# water_sensor_schematic.net
KiCad netlist of a schematic drawn in Altium Designer
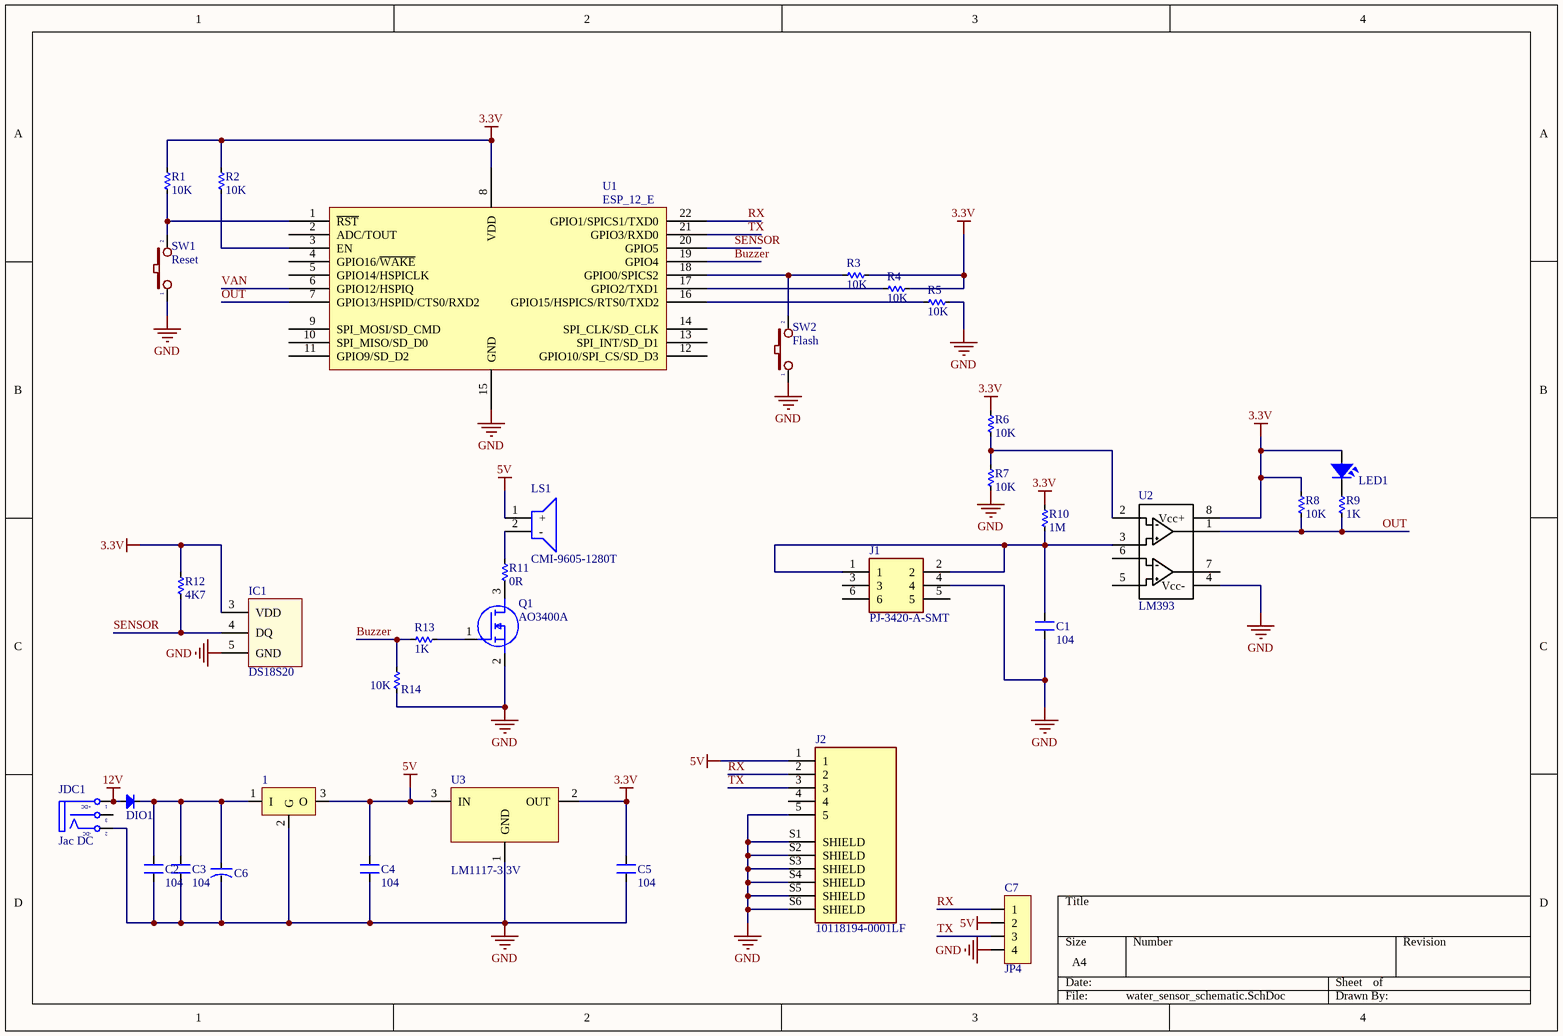
[diagram p0: water_sensor_schematic.SchDoc]

(export (version "E")
  (design (tool "Eeschema 10.0.6"))
  (components
    (comp (ref "1")
      (value "LM78xx")
      (footprint "TO252-123")
      (description "Positive Voltage Regulator")
      (fields (field (name "PUBLISHER") "Altium Limited"))
      (libsource (lib "LIBRARY") (part "LM78xx"))
    )
    (comp (ref "C1")
      (value "104")
      (footprint "SM-CAP-0805")
      (fields (field (name "DESIGNED BY") "VanDungEvn"))
      (libsource (lib "electronicvn-library1") (part "CN"))
    )
    (comp (ref "C2")
      (value "104")
      (footprint "SM-CAP-0805")
      (fields (field (name "DESIGNED BY") "VanDungEvn"))
      (libsource (lib "electronicvn-library1") (part "CN"))
    )
    (comp (ref "C3")
      (value "104")
      (footprint "SM-CAP-0805")
      (fields (field (name "DESIGNED BY") "VanDungEvn"))
      (libsource (lib "electronicvn-library1") (part "CN"))
    )
    (comp (ref "C4")
      (value "104")
      (footprint "SM-CAP-0805")
      (fields (field (name "DESIGNED BY") "VanDungEvn"))
      (libsource (lib "electronicvn-library1") (part "CN"))
    )
    (comp (ref "C5")
      (value "104")
      (footprint "SM-CAP-0805")
      (fields (field (name "DESIGNED BY") "VanDungEvn"))
      (libsource (lib "electronicvn-library1") (part "CN"))
    )
    (comp (ref "C6")
      (value "CN-ALU-SMD")
      (footprint "CAP-ALU-SMD-4.5x5x1.4")
      (description "Polarized Capacitor (Axial)")
      (fields (field (name "PUBLISHER") "Altium Limited"))
      (libsource (lib "LIBTanCN") (part "CN-ALU-SMD"))
    )
    (comp (ref "C7")
      (value "JP4")
      (footprint "JP4-C1T")
      (description "WR-PHD 2.54 mm Angled Socket Header")
      (fields
        (field (name "MANUFACTURER") "Würth Elektronik eiSos GmbH")
        (field (name "PARTNO") "613004143121")
        (field (name "CREATED BY") "Karrer Zheng")
      )
      (libsource (lib "LIBRARY") (part "JP4"))
    )
    (comp (ref "DIO1")
      (value "Diode SMD")
      (footprint "DIO-SMD-106")
      (description "Default Diode")
      (fields (field (name "PUBLISHER") "Altium Limited"))
      (libsource (lib "LIBRARY") (part "Diode SMD"))
    )
    (comp (ref "IC1")
      (value "DS18S20")
      (footprint "DS18S20")
      (description "High Precision  1-Wire® Digital Thermometer")
      (libsource (lib "LIBTanCN") (part "DS18S20"))
    )
    (comp (ref "J1")
      (value "PJ-3420-A-SMT")
      (footprint "SamacSys:PJ3420ASMT")
      (description "Connector")
      (libsource (lib "*") (part "PJ-3420-A-SMT"))
    )
    (comp (ref "J2")
      (value "10118194-0001LF")
      (footprint "AMPHENOL_10118194-0001LF")
      (description "USB - micro B USB 2.0 Receptacle Connector 5 Position Surface Mount, Right Angle; Through Hole")
      (fields (field (name "MF") "Amphenol ICC"))
      (libsource (lib "10118194-0001LF") (part "10118194-0001LF"))
    )
    (comp (ref "JDC1")
      (value "Jac DC")
      (footprint "DC3")
      (description "Jac DC input")
      (libsource (lib "LIBRARY") (part "DCIN"))
    )
    (comp (ref "LED1") (value "LED") (footprint "LED-0805-Blue") (libsource (lib "LIBRARY") (part "LED SMD")))
    (comp (ref "LS1")
      (value "CMI-9605-1280T")
      (footprint "SamacSys:CMI96051280T")
      (description "Loudspeaker or Buzzer")
      (fields (field (name "MOUSER PART NUMBER") "490-CMI-9605-1280T"))
      (libsource (lib "*") (part "CMI-9605-1280T"))
    )
    (comp (ref "Q1")
      (value "AO3400A")
      (footprint "SamacSys:SOT95P280X125-3N")
      (description "MOSFET (N-Channel)")
      (libsource (lib "SamacSys") (part "AO3400A"))
    )
    (comp (ref "R1")
      (value "10K")
      (footprint "RES-SMD-0805")
      (description "Resistor")
      (fields
        (field (name "MANUFACTURER") "Generic Components")
        (field (name "PUBLISHER") "Altium Hobart Technology Centre")
      )
      (libsource (lib "LIBRARY") (part "Res-SMD"))
    )
    (comp (ref "R2")
      (value "10K")
      (footprint "RES-SMD-0805")
      (description "Resistor")
      (fields
        (field (name "MANUFACTURER") "Generic Components")
        (field (name "PUBLISHER") "Altium Hobart Technology Centre")
      )
      (libsource (lib "LIBRARY") (part "Res-SMD"))
    )
    (comp (ref "R3")
      (value "10K")
      (footprint "RES-SMD-0805")
      (description "Resistor")
      (fields
        (field (name "MANUFACTURER") "Generic Components")
        (field (name "PUBLISHER") "Altium Hobart Technology Centre")
      )
      (libsource (lib "LIBRARY") (part "Res-SMD"))
    )
    (comp (ref "R4")
      (value "10K")
      (footprint "RES-SMD-0805")
      (description "Resistor")
      (fields
        (field (name "MANUFACTURER") "Generic Components")
        (field (name "PUBLISHER") "Altium Hobart Technology Centre")
      )
      (libsource (lib "LIBRARY") (part "Res-SMD"))
    )
    (comp (ref "R5")
      (value "10K")
      (footprint "RES-SMD-0805")
      (description "Resistor")
      (fields
        (field (name "MANUFACTURER") "Generic Components")
        (field (name "PUBLISHER") "Altium Hobart Technology Centre")
      )
      (libsource (lib "LIBRARY") (part "Res-SMD"))
    )
    (comp (ref "R6")
      (value "10K")
      (footprint "RES-SMD-0805")
      (description "Resistor")
      (fields
        (field (name "MANUFACTURER") "Generic Components")
        (field (name "PUBLISHER") "Altium Hobart Technology Centre")
      )
      (libsource (lib "LIBRARY") (part "Res-SMD"))
    )
    (comp (ref "R7")
      (value "10K")
      (footprint "RES-SMD-0805")
      (description "Resistor")
      (fields
        (field (name "MANUFACTURER") "Generic Components")
        (field (name "PUBLISHER") "Altium Hobart Technology Centre")
      )
      (libsource (lib "LIBRARY") (part "Res-SMD"))
    )
    (comp (ref "R8")
      (value "10K")
      (footprint "RES-SMD-0805")
      (description "Resistor")
      (fields
        (field (name "MANUFACTURER") "Generic Components")
        (field (name "PUBLISHER") "Altium Hobart Technology Centre")
      )
      (libsource (lib "LIBRARY") (part "Res-SMD"))
    )
    (comp (ref "R9")
      (value "1K")
      (footprint "RES-SMD-0805")
      (description "Resistor")
      (fields
        (field (name "MANUFACTURER") "Generic Components")
        (field (name "PUBLISHER") "Altium Hobart Technology Centre")
      )
      (libsource (lib "LIBRARY") (part "Res-SMD"))
    )
    (comp (ref "R10")
      (value "1M")
      (footprint "RES-SMD-0805")
      (description "Resistor")
      (fields
        (field (name "MANUFACTURER") "Generic Components")
        (field (name "PUBLISHER") "Altium Hobart Technology Centre")
      )
      (libsource (lib "LIBRARY") (part "Res-SMD"))
    )
    (comp (ref "R11")
      (value "0R")
      (footprint "RES-SMD-0805")
      (description "Resistor")
      (fields
        (field (name "MANUFACTURER") "Generic Components")
        (field (name "PUBLISHER") "Altium Hobart Technology Centre")
      )
      (libsource (lib "LIBRARY") (part "Res-SMD"))
    )
    (comp (ref "R12")
      (value "4K7")
      (footprint "RES-SMD-0805")
      (description "Resistor")
      (fields
        (field (name "MANUFACTURER") "Generic Components")
        (field (name "PUBLISHER") "Altium Hobart Technology Centre")
      )
      (libsource (lib "LIBRARY") (part "Res-SMD"))
    )
    (comp (ref "R13")
      (value "1K")
      (footprint "RES-SMD-0805")
      (description "Resistor")
      (fields
        (field (name "MANUFACTURER") "Generic Components")
        (field (name "PUBLISHER") "Altium Hobart Technology Centre")
      )
      (libsource (lib "LIBRARY") (part "Res-SMD"))
    )
    (comp (ref "R14")
      (value "10K")
      (footprint "RES-SMD-0805")
      (description "Resistor")
      (fields
        (field (name "MANUFACTURER") "Generic Components")
        (field (name "PUBLISHER") "Altium Hobart Technology Centre")
      )
      (libsource (lib "LIBRARY") (part "Res-SMD"))
    )
    (comp (ref "SW1")
      (value "Reset")
      (footprint "SW1-SMD")
      (description "Switch button 2 pin")
      (libsource (lib "LIBRARY") (part "SW2"))
    )
    (comp (ref "SW2")
      (value "Flash")
      (footprint "SW-DIP1-1")
      (description "Switch button 2 pin")
      (libsource (lib "LIBRARY") (part "SW2"))
    )
    (comp (ref "U1")
      (value "ESP_12_E")
      (footprint "ESP_12_E")
      (description "ESP-12 Wi-Fi Module by AI-Thinker")
      (libsource (lib "ESP8266") (part "ESP_12_E"))
    )
    (comp (ref "U2")
      (value "LM393")
      (footprint "SO8")
      (description "IC DUAL COMPARATOR")
      (libsource (lib "LIBRARY") (part "LM393"))
    )
    (comp (ref "U3")
      (value "LM1117-3.3V")
      (footprint "SOT223")
      (description "800mA Low-Dropout Linear Regulator")
      (fields (field (name "CREATOR") "Nguyen Ba Bien"))
      (libsource (lib "LIBRARY") (part "LM1117"))
    )
  )
  (nets
    (net (code "1") (name "/Buzzer") (class "Default")
      (node (ref "R13") (pin "2") (pinfunction "2_2") (pintype "passive"))
      (node (ref "R14") (pin "2") (pinfunction "2_2") (pintype "passive"))
      (node (ref "U1") (pin "19") (pinfunction "GPIO4_19") (pintype "passive"))
    )
    (net (code "2") (name "/OUT") (class "Default")
      (node (ref "R8") (pin "2") (pinfunction "2_2") (pintype "passive"))
      (node (ref "R9") (pin "2") (pinfunction "2_2") (pintype "passive"))
      (node (ref "U1") (pin "7") (pinfunction "GPIO13/HSPID/CTS0/RXD2_7") (pintype "passive"))
      (node (ref "U2") (pin "1") (pintype "passive"))
    )
    (net (code "3") (name "/RX") (class "Default")
      (node (ref "C7") (pin "1") (pinfunction "1_1") (pintype "passive"))
      (node (ref "J2") (pin "2") (pinfunction "2_2") (pintype "passive"))
      (node (ref "U1") (pin "22") (pinfunction "GPIO1/SPICS1/TXD0_22") (pintype "passive"))
    )
    (net (code "4") (name "/SENSOR") (class "Default")
      (node (ref "IC1") (pin "4") (pinfunction "DQ_4") (pintype "passive"))
      (node (ref "R12") (pin "2") (pinfunction "2_2") (pintype "passive"))
      (node (ref "U1") (pin "20") (pinfunction "GPIO5_20") (pintype "passive"))
    )
    (net (code "5") (name "/TX") (class "Default")
      (node (ref "C7") (pin "3") (pinfunction "3_3") (pintype "passive"))
      (node (ref "J2") (pin "3") (pinfunction "3_3") (pintype "passive"))
      (node (ref "U1") (pin "21") (pinfunction "GPIO3/RXD0_21") (pintype "passive"))
    )
    (net (code "6") (name "/VAN") (class "Default")
      (node (ref "U1") (pin "6") (pinfunction "GPIO12/HSPIQ_6") (pintype "passive"))
    )
    (net (code "7") (name "3.3V") (class "Default")
      (node (ref "C5") (pin "2") (pinfunction "2_2") (pintype "passive"))
      (node (ref "IC1") (pin "3") (pinfunction "VDD_3") (pintype "passive"))
      (node (ref "LED1") (pin "1") (pinfunction "1_1") (pintype "passive"))
      (node (ref "R1") (pin "1") (pinfunction "1_1") (pintype "passive"))
      (node (ref "R10") (pin "1") (pinfunction "1_1") (pintype "passive"))
      (node (ref "R12") (pin "1") (pinfunction "1_1") (pintype "passive"))
      (node (ref "R2") (pin "1") (pinfunction "1_1") (pintype "passive"))
      (node (ref "R3") (pin "1") (pinfunction "1_1") (pintype "passive"))
      (node (ref "R4") (pin "1") (pinfunction "1_1") (pintype "passive"))
      (node (ref "R6") (pin "1") (pinfunction "1_1") (pintype "passive"))
      (node (ref "R8") (pin "1") (pinfunction "1_1") (pintype "passive"))
      (node (ref "U1") (pin "8") (pinfunction "VDD_8") (pintype "passive"))
      (node (ref "U2") (pin "8") (pinfunction "Vcc+_8") (pintype "passive"))
      (node (ref "U3") (pin "2") (pinfunction "OUT_2") (pintype "passive"))
    )
    (net (code "8") (name "5V") (class "Default")
      (node (ref "1") (pin "3") (pinfunction "O_3") (pintype "power_in"))
      (node (ref "C4") (pin "2") (pinfunction "2_2") (pintype "passive"))
      (node (ref "C7") (pin "2") (pinfunction "2_2") (pintype "passive"))
      (node (ref "J2") (pin "1") (pinfunction "1_1") (pintype "passive"))
      (node (ref "LS1") (pin "1") (pinfunction "+_1") (pintype "passive"))
      (node (ref "U3") (pin "3") (pinfunction "IN_3") (pintype "passive"))
    )
    (net (code "9") (name "12V") (class "Default")
      (node (ref "DIO1") (pin "1") (pinfunction "A_1") (pintype "passive"))
      (node (ref "JDC1") (pin "1") (pinfunction "T_1") (pintype "passive"))
    )
    (net (code "10") (name "GND") (class "Default")
      (node (ref "1") (pin "2") (pinfunction "G_2") (pintype "power_in"))
      (node (ref "C1") (pin "1") (pinfunction "1_1") (pintype "passive"))
      (node (ref "C2") (pin "1") (pinfunction "1_1") (pintype "passive"))
      (node (ref "C3") (pin "1") (pinfunction "1_1") (pintype "passive"))
      (node (ref "C4") (pin "1") (pinfunction "1_1") (pintype "passive"))
      (node (ref "C5") (pin "1") (pinfunction "1_1") (pintype "passive"))
      (node (ref "C6") (pin "2") (pinfunction "2_2") (pintype "passive"))
      (node (ref "C7") (pin "4") (pinfunction "4_4") (pintype "passive"))
      (node (ref "IC1") (pin "5") (pinfunction "GND_5") (pintype "passive"))
      (node (ref "J1") (pin "4") (pinfunction "4_4") (pintype "passive"))
      (node (ref "J2") (pin "5") (pinfunction "5_5") (pintype "passive"))
      (node (ref "J2") (pin "S1") (pinfunction "SHIELD_S1") (pintype "passive"))
      (node (ref "J2") (pin "S2") (pinfunction "SHIELD_S2") (pintype "passive"))
      (node (ref "J2") (pin "S3") (pinfunction "SHIELD_S3") (pintype "passive"))
      (node (ref "J2") (pin "S4") (pinfunction "SHIELD_S4") (pintype "passive"))
      (node (ref "J2") (pin "S5") (pinfunction "SHIELD_S5") (pintype "passive"))
      (node (ref "J2") (pin "S6") (pinfunction "SHIELD_S6") (pintype "passive"))
      (node (ref "JDC1") (pin "2") (pinfunction "TN_2") (pintype "passive"))
      (node (ref "Q1") (pin "2") (pinfunction "S_2") (pintype "passive"))
      (node (ref "R14") (pin "1") (pinfunction "1_1") (pintype "passive"))
      (node (ref "R5") (pin "1") (pinfunction "1_1") (pintype "passive"))
      (node (ref "R7") (pin "2") (pinfunction "2_2") (pintype "passive"))
      (node (ref "SW1") (pin "1") (pinfunction "1_1") (pintype "passive"))
      (node (ref "SW2") (pin "1") (pinfunction "1_1") (pintype "passive"))
      (node (ref "U1") (pin "15") (pinfunction "GND_15") (pintype "passive"))
      (node (ref "U2") (pin "4") (pinfunction "Vcc-_4") (pintype "passive"))
      (node (ref "U3") (pin "1") (pinfunction "GND_1") (pintype "passive"))
    )
    (net (code "11") (name "Net-(1-I)") (class "Default")
      (node (ref "1") (pin "1") (pinfunction "I_1") (pintype "power_in"))
      (node (ref "C2") (pin "2") (pinfunction "2_2") (pintype "passive"))
      (node (ref "C3") (pin "2") (pinfunction "2_2") (pintype "passive"))
      (node (ref "C6") (pin "1") (pinfunction "1_1") (pintype "passive"))
      (node (ref "DIO1") (pin "2") (pinfunction "K_2") (pintype "passive"))
    )
    (net (code "12") (name "Net-(C1-Pad2)") (class "Default")
      (node (ref "C1") (pin "2") (pinfunction "2_2") (pintype "passive"))
      (node (ref "J1") (pin "1") (pinfunction "1_1") (pintype "passive"))
      (node (ref "J1") (pin "2") (pinfunction "2_2") (pintype "passive"))
      (node (ref "R10") (pin "2") (pinfunction "2_2") (pintype "passive"))
      (node (ref "U2") (pin "3") (pintype "passive"))
    )
    (net (code "13") (name "Net-(LED1-Pad2)") (class "Default")
      (node (ref "LED1") (pin "2") (pinfunction "2_2") (pintype "passive"))
      (node (ref "R9") (pin "1") (pinfunction "1_1") (pintype "passive"))
    )
    (net (code "14") (name "Net-(LS1--)") (class "Default")
      (node (ref "LS1") (pin "2") (pinfunction "-_2") (pintype "passive"))
      (node (ref "R11") (pin "1") (pinfunction "1_1") (pintype "passive"))
    )
    (net (code "15") (name "Net-(Q1-D)") (class "Default")
      (node (ref "Q1") (pin "3") (pinfunction "D_3") (pintype "passive"))
      (node (ref "R11") (pin "2") (pinfunction "2_2") (pintype "passive"))
    )
    (net (code "16") (name "Net-(Q1-G)") (class "Default")
      (node (ref "Q1") (pin "1") (pinfunction "G_1") (pintype "passive"))
      (node (ref "R13") (pin "1") (pinfunction "1_1") (pintype "passive"))
    )
    (net (code "17") (name "Net-(R6-Pad2)") (class "Default")
      (node (ref "R6") (pin "2") (pinfunction "2_2") (pintype "passive"))
      (node (ref "R7") (pin "1") (pinfunction "1_1") (pintype "passive"))
      (node (ref "U2") (pin "2") (pintype "passive"))
    )
    (net (code "18") (name "Net-(U1-EN)") (class "Default")
      (node (ref "R2") (pin "2") (pinfunction "2_2") (pintype "passive"))
      (node (ref "U1") (pin "3") (pinfunction "EN_3") (pintype "passive"))
    )
    (net (code "19") (name "Net-(U1-GPIO0{slash}SPICS2)") (class "Default")
      (node (ref "R3") (pin "2") (pinfunction "2_2") (pintype "passive"))
      (node (ref "SW2") (pin "2") (pinfunction "2_2") (pintype "passive"))
      (node (ref "U1") (pin "18") (pinfunction "GPIO0/SPICS2_18") (pintype "passive"))
    )
    (net (code "20") (name "Net-(U1-GPIO2{slash}TXD1)") (class "Default")
      (node (ref "R4") (pin "2") (pinfunction "2_2") (pintype "passive"))
      (node (ref "U1") (pin "17") (pinfunction "GPIO2/TXD1_17") (pintype "passive"))
    )
    (net (code "21") (name "Net-(U1-GPIO15{slash}HSPICS{slash}RTS0{slash}TXD2)") (class "Default")
      (node (ref "R5") (pin "2") (pinfunction "2_2") (pintype "passive"))
      (node (ref "U1") (pin "16") (pinfunction "GPIO15/HSPICS/RTS0/TXD2_16") (pintype "passive"))
    )
    (net (code "22") (name "Net-(U1-~{RST})") (class "Default")
      (node (ref "R1") (pin "2") (pinfunction "2_2") (pintype "passive"))
      (node (ref "SW1") (pin "2") (pinfunction "2_2") (pintype "passive"))
      (node (ref "U1") (pin "1") (pinfunction "~{RST}_1") (pintype "passive"))
    )
    (net (code "23") (name "unconnected-(J1-Pad3)") (class "Default")
      (node (ref "J1") (pin "3") (pinfunction "3_3") (pintype "passive"))
    )
    (net (code "24") (name "unconnected-(J1-Pad5)") (class "Default")
      (node (ref "J1") (pin "5") (pinfunction "5_5") (pintype "passive"))
    )
    (net (code "25") (name "unconnected-(J1-Pad6)") (class "Default")
      (node (ref "J1") (pin "6") (pinfunction "6_6") (pintype "passive"))
    )
    (net (code "26") (name "unconnected-(J2-Pad4)") (class "Default")
      (node (ref "J2") (pin "4") (pinfunction "4_4") (pintype "passive"))
    )
    (net (code "27") (name "unconnected-(JDC1-S-Pad3)") (class "Default")
      (node (ref "JDC1") (pin "3") (pinfunction "S_3") (pintype "power_in"))
    )
    (net (code "28") (name "unconnected-(U1-ADC{slash}TOUT-Pad2)") (class "Default")
      (node (ref "U1") (pin "2") (pinfunction "ADC/TOUT_2") (pintype "passive"))
    )
    (net (code "29") (name "unconnected-(U1-GPIO9{slash}SD_D2-Pad11)") (class "Default")
      (node (ref "U1") (pin "11") (pinfunction "GPIO9/SD_D2_11") (pintype "passive"))
    )
    (net (code "30") (name "unconnected-(U1-GPIO10{slash}SPI_CS{slash}SD_D3-Pad12)") (class "Default")
      (node (ref "U1") (pin "12") (pinfunction "GPIO10/SPI_CS/SD_D3_12") (pintype "passive"))
    )
    (net (code "31") (name "unconnected-(U1-GPIO14{slash}HSPICLK-Pad5)") (class "Default")
      (node (ref "U1") (pin "5") (pinfunction "GPIO14/HSPICLK_5") (pintype "passive"))
    )
    (net (code "32") (name "unconnected-(U1-GPIO16{slash}~{WAKE}-Pad4)") (class "Default")
      (node (ref "U1") (pin "4") (pinfunction "GPIO16/~{WAKE}_4") (pintype "passive"))
    )
    (net (code "33") (name "unconnected-(U1-SPI_CLK{slash}SD_CLK-Pad14)") (class "Default")
      (node (ref "U1") (pin "14") (pinfunction "SPI_CLK/SD_CLK_14") (pintype "passive"))
    )
    (net (code "34") (name "unconnected-(U1-SPI_INT{slash}SD_D1-Pad13)") (class "Default")
      (node (ref "U1") (pin "13") (pinfunction "SPI_INT/SD_D1_13") (pintype "passive"))
    )
    (net (code "35") (name "unconnected-(U1-SPI_MISO{slash}SD_D0-Pad10)") (class "Default")
      (node (ref "U1") (pin "10") (pinfunction "SPI_MISO/SD_D0_10") (pintype "passive"))
    )
    (net (code "36") (name "unconnected-(U1-SPI_MOSI{slash}SD_CMD-Pad9)") (class "Default")
      (node (ref "U1") (pin "9") (pinfunction "SPI_MOSI/SD_CMD_9") (pintype "passive"))
    )
    (net (code "37") (name "unconnected-(U2-Pad5)") (class "Default")
      (node (ref "U2") (pin "5") (pintype "passive"))
    )
    (net (code "38") (name "unconnected-(U2-Pad6)") (class "Default")
      (node (ref "U2") (pin "6") (pintype "passive"))
    )
    (net (code "39") (name "unconnected-(U2-Pad7)") (class "Default")
      (node (ref "U2") (pin "7") (pintype "passive"))
    )
  )
)
